# Power.net
KiCad netlist of a schematic drawn in Altium Designer
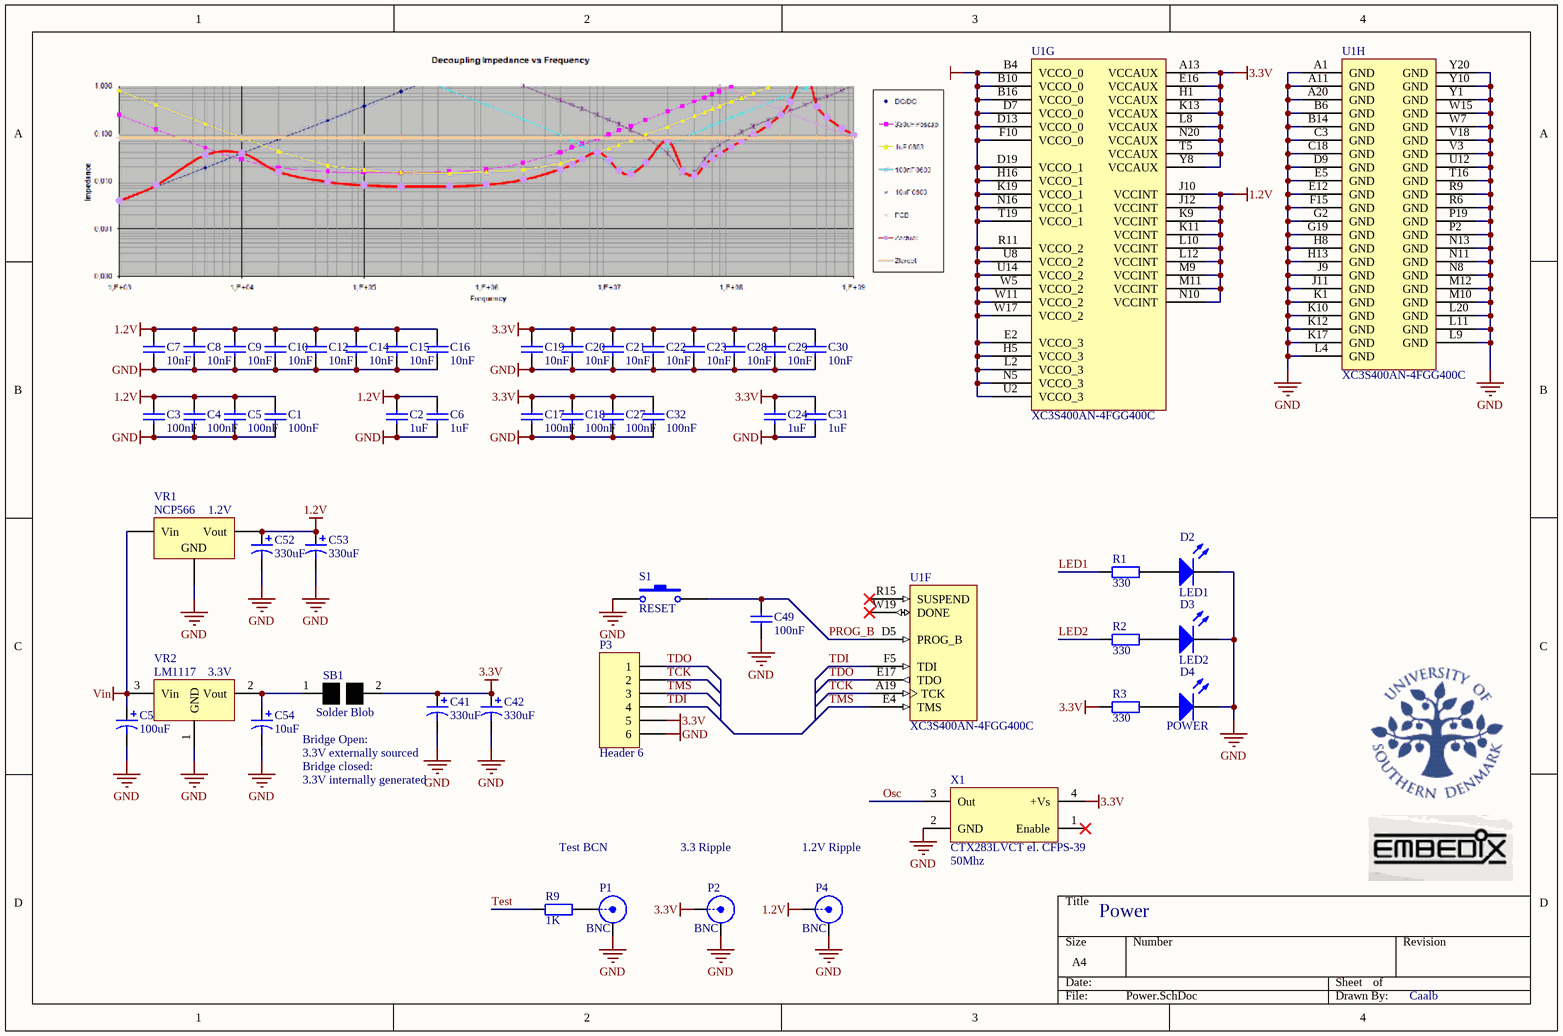
[diagram p0: Power.SchDoc]

(export (version "E")
  (design (tool "Eeschema 10.0.6"))
  (components
    (comp (ref "C1")
      (value "100nF")
      (footprint "0603")
      (description "!Capacitor")
      (fields (field (name "Comment") "Cap") (field (name "PUBLISHER") "Altium Limited"))
      (libsource (lib "Miscellaneous Devices") (part "Cap"))
    )
    (comp (ref "C2")
      (value "1uF")
      (footprint "0603")
      (description "!Capacitor")
      (fields (field (name "Comment") "Cap") (field (name "PUBLISHER") "Altium Limited"))
      (libsource (lib "Miscellaneous Devices") (part "Cap"))
    )
    (comp (ref "C3")
      (value "100nF")
      (footprint "0603")
      (description "!Capacitor")
      (fields (field (name "Comment") "Cap") (field (name "PUBLISHER") "Altium Limited"))
      (libsource (lib "Miscellaneous Devices") (part "Cap"))
    )
    (comp (ref "C4")
      (value "100nF")
      (footprint "0603")
      (description "!Capacitor")
      (fields (field (name "Comment") "Cap") (field (name "PUBLISHER") "Altium Limited"))
      (libsource (lib "Miscellaneous Devices") (part "Cap"))
    )
    (comp (ref "C5")
      (value "100nF")
      (footprint "0603")
      (description "!Capacitor")
      (fields (field (name "Comment") "Cap") (field (name "PUBLISHER") "Altium Limited"))
      (libsource (lib "Miscellaneous Devices") (part "Cap"))
    )
    (comp (ref "C6")
      (value "1uF")
      (footprint "0603")
      (description "!Capacitor")
      (fields (field (name "Comment") "Cap") (field (name "PUBLISHER") "Altium Limited"))
      (libsource (lib "Miscellaneous Devices") (part "Cap"))
    )
    (comp (ref "C7")
      (value "10nF")
      (footprint "0603")
      (description "!Capacitor")
      (fields (field (name "Comment") "Cap") (field (name "PUBLISHER") "Altium Limited"))
      (libsource (lib "Miscellaneous Devices") (part "Cap"))
    )
    (comp (ref "C8")
      (value "10nF")
      (footprint "0603")
      (description "!Capacitor")
      (fields (field (name "Comment") "Cap") (field (name "PUBLISHER") "Altium Limited"))
      (libsource (lib "Miscellaneous Devices") (part "Cap"))
    )
    (comp (ref "C9")
      (value "10nF")
      (footprint "0603")
      (description "!Capacitor")
      (fields (field (name "Comment") "Cap") (field (name "PUBLISHER") "Altium Limited"))
      (libsource (lib "Miscellaneous Devices") (part "Cap"))
    )
    (comp (ref "C10")
      (value "10nF")
      (footprint "0603")
      (description "!Capacitor")
      (fields (field (name "Comment") "Cap") (field (name "PUBLISHER") "Altium Limited"))
      (libsource (lib "Miscellaneous Devices") (part "Cap"))
    )
    (comp (ref "C12")
      (value "10nF")
      (footprint "0603")
      (description "!Capacitor")
      (fields (field (name "Comment") "Cap") (field (name "PUBLISHER") "Altium Limited"))
      (libsource (lib "Miscellaneous Devices") (part "Cap"))
    )
    (comp (ref "C14")
      (value "10nF")
      (footprint "0603")
      (description "!Capacitor")
      (fields (field (name "Comment") "Cap") (field (name "PUBLISHER") "Altium Limited"))
      (libsource (lib "Miscellaneous Devices") (part "Cap"))
    )
    (comp (ref "C15")
      (value "10nF")
      (footprint "0603")
      (description "!Capacitor")
      (fields (field (name "Comment") "Cap") (field (name "PUBLISHER") "Altium Limited"))
      (libsource (lib "Miscellaneous Devices") (part "Cap"))
    )
    (comp (ref "C16")
      (value "10nF")
      (footprint "0603")
      (description "!Capacitor")
      (fields (field (name "Comment") "Cap") (field (name "PUBLISHER") "Altium Limited"))
      (libsource (lib "Miscellaneous Devices") (part "Cap"))
    )
    (comp (ref "C17")
      (value "100nF")
      (footprint "0603")
      (description "!Capacitor")
      (fields (field (name "Comment") "Cap") (field (name "PUBLISHER") "Altium Limited"))
      (libsource (lib "Miscellaneous Devices") (part "Cap"))
    )
    (comp (ref "C18")
      (value "100nF")
      (footprint "0603")
      (description "!Capacitor")
      (fields (field (name "Comment") "Cap") (field (name "PUBLISHER") "Altium Limited"))
      (libsource (lib "Miscellaneous Devices") (part "Cap"))
    )
    (comp (ref "C19")
      (value "10nF")
      (footprint "0603")
      (description "!Capacitor")
      (fields (field (name "Comment") "Cap") (field (name "PUBLISHER") "Altium Limited"))
      (libsource (lib "Miscellaneous Devices") (part "Cap"))
    )
    (comp (ref "C20")
      (value "10nF")
      (footprint "0603")
      (description "!Capacitor")
      (fields (field (name "Comment") "Cap") (field (name "PUBLISHER") "Altium Limited"))
      (libsource (lib "Miscellaneous Devices") (part "Cap"))
    )
    (comp (ref "C21")
      (value "10nF")
      (footprint "0603")
      (description "!Capacitor")
      (fields (field (name "Comment") "Cap") (field (name "PUBLISHER") "Altium Limited"))
      (libsource (lib "Miscellaneous Devices") (part "Cap"))
    )
    (comp (ref "C22")
      (value "10nF")
      (footprint "0603")
      (description "!Capacitor")
      (fields (field (name "Comment") "Cap") (field (name "PUBLISHER") "Altium Limited"))
      (libsource (lib "Miscellaneous Devices") (part "Cap"))
    )
    (comp (ref "C23")
      (value "10nF")
      (footprint "0603")
      (description "!Capacitor")
      (fields (field (name "Comment") "Cap") (field (name "PUBLISHER") "Altium Limited"))
      (libsource (lib "Miscellaneous Devices") (part "Cap"))
    )
    (comp (ref "C24")
      (value "1uF")
      (footprint "0603")
      (description "!Capacitor")
      (fields (field (name "Comment") "Cap") (field (name "PUBLISHER") "Altium Limited"))
      (libsource (lib "Miscellaneous Devices") (part "Cap"))
    )
    (comp (ref "C27")
      (value "100nF")
      (footprint "0603")
      (description "!Capacitor")
      (fields (field (name "Comment") "Cap") (field (name "PUBLISHER") "Altium Limited"))
      (libsource (lib "Miscellaneous Devices") (part "Cap"))
    )
    (comp (ref "C28")
      (value "10nF")
      (footprint "0603")
      (description "!Capacitor")
      (fields (field (name "Comment") "Cap") (field (name "PUBLISHER") "Altium Limited"))
      (libsource (lib "Miscellaneous Devices") (part "Cap"))
    )
    (comp (ref "C29")
      (value "10nF")
      (footprint "0603")
      (description "!Capacitor")
      (fields (field (name "Comment") "Cap") (field (name "PUBLISHER") "Altium Limited"))
      (libsource (lib "Miscellaneous Devices") (part "Cap"))
    )
    (comp (ref "C30")
      (value "10nF")
      (footprint "0603")
      (description "!Capacitor")
      (fields (field (name "Comment") "Cap") (field (name "PUBLISHER") "Altium Limited"))
      (libsource (lib "Miscellaneous Devices") (part "Cap"))
    )
    (comp (ref "C31")
      (value "1uF")
      (footprint "0603")
      (description "!Capacitor")
      (fields (field (name "Comment") "Cap") (field (name "PUBLISHER") "Altium Limited"))
      (libsource (lib "Miscellaneous Devices") (part "Cap"))
    )
    (comp (ref "C32")
      (value "100nF")
      (footprint "0603")
      (description "!Capacitor")
      (fields (field (name "Comment") "Cap") (field (name "PUBLISHER") "Altium Limited"))
      (libsource (lib "Miscellaneous Devices") (part "Cap"))
    )
    (comp (ref "C41")
      (value "330uF")
      (footprint "Tantal size X")
      (description "!Polarized Capacitor (Radial)")
      (fields (field (name "Comment") "Cap Pol1") (field (name "PUBLISHER") "Altium Limited"))
      (libsource (lib "Miscellaneous Devices") (part "Cap Pol1"))
    )
    (comp (ref "C42")
      (value "330uF")
      (footprint "Tantal size X")
      (description "!Polarized Capacitor (Radial)")
      (fields (field (name "Comment") "Cap Pol1") (field (name "PUBLISHER") "Altium Limited"))
      (libsource (lib "Miscellaneous Devices") (part "Cap Pol1"))
    )
    (comp (ref "C49")
      (value "100nF")
      (footprint "0603")
      (description "!Capacitor")
      (fields (field (name "Comment") "Cap") (field (name "PUBLISHER") "Altium Limited"))
      (libsource (lib "") (part "Cap_1"))
    )
    (comp (ref "C51")
      (value "100uF")
      (footprint "Tantal size X")
      (description "!Polarized Capacitor (Radial)")
      (fields (field (name "Comment") "Cap Pol1") (field (name "PUBLISHER") "Altium Limited"))
      (libsource (lib "Miscellaneous Devices") (part "Cap Pol1"))
    )
    (comp (ref "C52")
      (value "330uF")
      (footprint "Tantal size X")
      (description "!Polarized Capacitor (Radial)")
      (fields (field (name "Comment") "Cap Pol1") (field (name "PUBLISHER") "Altium Limited"))
      (libsource (lib "Miscellaneous Devices") (part "Cap Pol1"))
    )
    (comp (ref "C53")
      (value "330uF")
      (footprint "Tantal size X")
      (description "!Polarized Capacitor (Radial)")
      (fields (field (name "Comment") "Cap Pol1") (field (name "PUBLISHER") "Altium Limited"))
      (libsource (lib "Miscellaneous Devices") (part "Cap Pol1"))
    )
    (comp (ref "C54")
      (value "10uF")
      (footprint "1206Pol")
      (description "!Polarized Capacitor (Radial)")
      (fields (field (name "Comment") "Cap Pol1") (field (name "PUBLISHER") "Altium Limited"))
      (libsource (lib "Miscellaneous Devices") (part "Cap Pol1"))
    )
    (comp (ref "D2")
      (value "LED1")
      (footprint "LED0805")
      (description "LED")
      (fields (field (name "PUBLISHER") "Altium Limited"))
      (libsource (lib "Miscellaneous Devices") (part "LED0"))
    )
    (comp (ref "D3")
      (value "LED2")
      (footprint "LED0805")
      (description "LED")
      (fields (field (name "PUBLISHER") "Altium Limited"))
      (libsource (lib "Miscellaneous Devices") (part "LED0"))
    )
    (comp (ref "D4")
      (value "POWER")
      (footprint "LED0805")
      (description "LED")
      (fields (field (name "PUBLISHER") "Altium Limited"))
      (libsource (lib "Miscellaneous Devices") (part "LED0"))
    )
    (comp (ref "P1")
      (value "BNC")
      (footprint "Miniature Coaxial Connectors")
      (description "Miniature Coaxial Connectors")
      (fields (field (name "PUBLISHER") "Altium Limited"))
      (libsource (lib "Miscellaneous Connectors") (part "BNC"))
    )
    (comp (ref "P2")
      (value "BNC")
      (footprint "Miniature Coaxial Connectors")
      (description "Miniature Coaxial Connectors")
      (fields (field (name "PUBLISHER") "Altium Limited"))
      (libsource (lib "Miscellaneous Connectors") (part "BNC"))
    )
    (comp (ref "P3")
      (value "Header 6")
      (footprint "HDR1X6")
      (description "Header, 6-Pin")
      (fields (field (name "PUBLISHER") "Altium Limited"))
      (libsource (lib "Miscellaneous Connectors") (part "Header 6"))
    )
    (comp (ref "P4")
      (value "BNC")
      (footprint "Miniature Coaxial Connectors")
      (description "Miniature Coaxial Connectors")
      (fields (field (name "PUBLISHER") "Altium Limited"))
      (libsource (lib "Miscellaneous Connectors") (part "BNC"))
    )
    (comp (ref "R1")
      (value "330")
      (footprint "0805")
      (description "!Resistor")
      (fields (field (name "Comment") "Res2") (field (name "PUBLISHER") "Altium Limited"))
      (libsource (lib "") (part "Res2_1"))
    )
    (comp (ref "R2")
      (value "330")
      (footprint "0805")
      (description "!Resistor")
      (fields (field (name "Comment") "Res2") (field (name "PUBLISHER") "Altium Limited"))
      (libsource (lib "") (part "Res2_1"))
    )
    (comp (ref "R3")
      (value "330")
      (footprint "0805")
      (description "!Resistor")
      (fields (field (name "Comment") "Res2") (field (name "PUBLISHER") "Altium Limited"))
      (libsource (lib "") (part "Res2_1"))
    )
    (comp (ref "R9")
      (value "1K")
      (footprint "0603")
      (description "!Resistor")
      (fields (field (name "Comment") "Res2") (field (name "PUBLISHER") "Altium Limited"))
      (libsource (lib "Miscellaneous Devices") (part "Res2"))
    )
    (comp (ref "S1")
      (value "RESET")
      (footprint "B3U-3000P")
      (description "Switch")
      (fields (field (name "PUBLISHER") "Altium Limited"))
      (libsource (lib "Miscellaneous Devices") (part "SW-PB"))
    )
    (comp (ref "SB1")
      (value "Solder Blob")
      (footprint "0805 v.solder_blob")
      (fields
        (field (name "ALTIUM_UNNAMED_1") "Bridge Open:")
        (field (name "ALTIUM_UNNAMED_2") "Bridge closed:")
        (field (name "ALTIUM_UNNAMED_3") "3.3V externally sourced")
        (field (name "ALTIUM_UNNAMED_4") "3.3V internally generated")
      )
      (libsource (lib "DivLib") (part "Jumper"))
    )
    (comp (ref "U1")
      (value "XC3S400AN-4FGG400C")
      (footprint "FGG400")
      (fields (field (name "PUBLISHER") "Altium Limited"))
      (libsource (lib "Xilinx Spartan-3AN") (part "XC3S400AN-4FGG400C"))
    )
    (comp (ref "VR1")
      (value "NCP566")
      (footprint "SOT-223")
      (description "Volt Reg NCP566")
      (fields (field (name "ALTIUM_VALUE") "1.2V") (field (name "PUBLISHER") "Altium Limited"))
      (libsource (lib "Miscellaneous Devices") (part "Volt Reg"))
    )
    (comp (ref "VR2")
      (value "LM1117")
      (footprint "SOT-223")
      (description "800mA Low-Dropout Linear Regulator")
      (fields (field (name "ALTIUM_VALUE") "3.3V"))
      (libsource (lib "DivLib") (part "LM1117"))
    )
    (comp (ref "X1")
      (value "CTX283LVCT el. CFPS-39")
      (footprint "CB3LV-3C-50M0000")
      (description "3.3V, ultra minature surface mount oscillator")
      (fields (field (name "ALTIUM_VALUE") "50Mhz"))
      (libsource (lib "DivLib") (part "CFPS-39"))
    )
  )
  (nets
    (net (code "1") (name "/LED1") (class "Default")
      (node (ref "R1") (pin "2") (pinfunction "2_2") (pintype "passive"))
    )
    (net (code "2") (name "/LED2") (class "Default")
      (node (ref "R2") (pin "2") (pinfunction "2_2") (pintype "passive"))
    )
    (net (code "3") (name "/Osc") (class "Default")
      (node (ref "X1") (pin "3") (pinfunction "Out_3") (pintype "power_in"))
    )
    (net (code "4") (name "/PROG_B") (class "Default")
      (node (ref "C49") (pin "2") (pinfunction "2_2") (pintype "passive"))
      (node (ref "S1") (pin "2") (pinfunction "2_2") (pintype "passive"))
      (node (ref "U1") (pin "D5") (pinfunction "PROG_B_D5") (pintype "input"))
    )
    (net (code "5") (name "/TCK") (class "Default")
      (node (ref "P3") (pin "2") (pinfunction "2_2") (pintype "passive"))
      (node (ref "U1") (pin "A19") (pinfunction "TCK_A19") (pintype "input"))
    )
    (net (code "6") (name "/TDI") (class "Default")
      (node (ref "P3") (pin "4") (pinfunction "4_4") (pintype "passive"))
      (node (ref "U1") (pin "F5") (pinfunction "TDI_F5") (pintype "input"))
    )
    (net (code "7") (name "/TDO") (class "Default")
      (node (ref "P3") (pin "1") (pinfunction "1_1") (pintype "passive"))
      (node (ref "U1") (pin "E17") (pinfunction "TDO_E17") (pintype "output"))
    )
    (net (code "8") (name "/TMS") (class "Default")
      (node (ref "P3") (pin "3") (pinfunction "3_3") (pintype "passive"))
      (node (ref "U1") (pin "E4") (pinfunction "TMS_E4") (pintype "input"))
    )
    (net (code "9") (name "/Test") (class "Default")
      (node (ref "R9") (pin "1") (pinfunction "1_1") (pintype "passive"))
    )
    (net (code "10") (name "1.2V") (class "Default")
      (node (ref "C1") (pin "2") (pinfunction "2_2") (pintype "passive"))
      (node (ref "C10") (pin "2") (pinfunction "2_2") (pintype "passive"))
      (node (ref "C12") (pin "2") (pinfunction "2_2") (pintype "passive"))
      (node (ref "C14") (pin "2") (pinfunction "2_2") (pintype "passive"))
      (node (ref "C15") (pin "2") (pinfunction "2_2") (pintype "passive"))
      (node (ref "C16") (pin "2") (pinfunction "2_2") (pintype "passive"))
      (node (ref "C2") (pin "2") (pinfunction "2_2") (pintype "passive"))
      (node (ref "C3") (pin "2") (pinfunction "2_2") (pintype "passive"))
      (node (ref "C4") (pin "2") (pinfunction "2_2") (pintype "passive"))
      (node (ref "C5") (pin "2") (pinfunction "2_2") (pintype "passive"))
      (node (ref "C52") (pin "1") (pinfunction "1_1") (pintype "passive"))
      (node (ref "C53") (pin "1") (pinfunction "1_1") (pintype "passive"))
      (node (ref "C6") (pin "2") (pinfunction "2_2") (pintype "passive"))
      (node (ref "C7") (pin "2") (pinfunction "2_2") (pintype "passive"))
      (node (ref "C8") (pin "2") (pinfunction "2_2") (pintype "passive"))
      (node (ref "C9") (pin "2") (pinfunction "2_2") (pintype "passive"))
      (node (ref "P4") (pin "1") (pinfunction "X_1") (pintype "passive"))
      (node (ref "U1") (pin "J10") (pinfunction "VCCINT_J10") (pintype "power_in"))
      (node (ref "U1") (pin "J12") (pinfunction "VCCINT_J12") (pintype "power_in"))
      (node (ref "U1") (pin "K11") (pinfunction "VCCINT_K11") (pintype "power_in"))
      (node (ref "U1") (pin "K9") (pinfunction "VCCINT_K9") (pintype "power_in"))
      (node (ref "U1") (pin "L10") (pinfunction "VCCINT_L10") (pintype "power_in"))
      (node (ref "U1") (pin "L12") (pinfunction "VCCINT_L12") (pintype "power_in"))
      (node (ref "U1") (pin "M11") (pinfunction "VCCINT_M11") (pintype "power_in"))
      (node (ref "U1") (pin "M9") (pinfunction "VCCINT_M9") (pintype "power_in"))
      (node (ref "U1") (pin "N10") (pinfunction "VCCINT_N10") (pintype "power_in"))
      (node (ref "VR1") (pin "3") (pinfunction "Vout_3") (pintype "passive"))
    )
    (net (code "11") (name "3.3V") (class "Default")
      (node (ref "C17") (pin "2") (pinfunction "2_2") (pintype "passive"))
      (node (ref "C18") (pin "2") (pinfunction "2_2") (pintype "passive"))
      (node (ref "C19") (pin "2") (pinfunction "2_2") (pintype "passive"))
      (node (ref "C20") (pin "2") (pinfunction "2_2") (pintype "passive"))
      (node (ref "C21") (pin "2") (pinfunction "2_2") (pintype "passive"))
      (node (ref "C22") (pin "2") (pinfunction "2_2") (pintype "passive"))
      (node (ref "C23") (pin "2") (pinfunction "2_2") (pintype "passive"))
      (node (ref "C24") (pin "2") (pinfunction "2_2") (pintype "passive"))
      (node (ref "C27") (pin "2") (pinfunction "2_2") (pintype "passive"))
      (node (ref "C28") (pin "2") (pinfunction "2_2") (pintype "passive"))
      (node (ref "C29") (pin "2") (pinfunction "2_2") (pintype "passive"))
      (node (ref "C30") (pin "2") (pinfunction "2_2") (pintype "passive"))
      (node (ref "C31") (pin "2") (pinfunction "2_2") (pintype "passive"))
      (node (ref "C32") (pin "2") (pinfunction "2_2") (pintype "passive"))
      (node (ref "C41") (pin "1") (pinfunction "1_1") (pintype "passive"))
      (node (ref "C42") (pin "1") (pinfunction "1_1") (pintype "passive"))
      (node (ref "P2") (pin "1") (pinfunction "X_1") (pintype "passive"))
      (node (ref "P3") (pin "5") (pinfunction "5_5") (pintype "passive"))
      (node (ref "R3") (pin "2") (pinfunction "2_2") (pintype "passive"))
      (node (ref "SB1") (pin "2") (pinfunction "2_2") (pintype "passive"))
      (node (ref "U1") (pin "A13") (pinfunction "VCCAUX_A13") (pintype "power_in"))
      (node (ref "U1") (pin "B10") (pinfunction "VCCO_0_B10") (pintype "power_in"))
      (node (ref "U1") (pin "B16") (pinfunction "VCCO_0_B16") (pintype "power_in"))
      (node (ref "U1") (pin "B4") (pinfunction "VCCO_0_B4") (pintype "power_in"))
      (node (ref "U1") (pin "D13") (pinfunction "VCCO_0_D13") (pintype "power_in"))
      (node (ref "U1") (pin "D19") (pinfunction "VCCO_1_D19") (pintype "power_in"))
      (node (ref "U1") (pin "D7") (pinfunction "VCCO_0_D7") (pintype "power_in"))
      (node (ref "U1") (pin "E16") (pinfunction "VCCAUX_E16") (pintype "power_in"))
      (node (ref "U1") (pin "E2") (pinfunction "VCCO_3_E2") (pintype "power_in"))
      (node (ref "U1") (pin "F10") (pinfunction "VCCO_0_F10") (pintype "power_in"))
      (node (ref "U1") (pin "H1") (pinfunction "VCCAUX_H1") (pintype "power_in"))
      (node (ref "U1") (pin "H16") (pinfunction "VCCO_1_H16") (pintype "power_in"))
      (node (ref "U1") (pin "H5") (pinfunction "VCCO_3_H5") (pintype "power_in"))
      (node (ref "U1") (pin "K13") (pinfunction "VCCAUX_K13") (pintype "power_in"))
      (node (ref "U1") (pin "K19") (pinfunction "VCCO_1_K19") (pintype "power_in"))
      (node (ref "U1") (pin "L2") (pinfunction "VCCO_3_L2") (pintype "power_in"))
      (node (ref "U1") (pin "L8") (pinfunction "VCCAUX_L8") (pintype "power_in"))
      (node (ref "U1") (pin "N16") (pinfunction "VCCO_1_N16") (pintype "power_in"))
      (node (ref "U1") (pin "N20") (pinfunction "VCCAUX_N20") (pintype "power_in"))
      (node (ref "U1") (pin "N5") (pinfunction "VCCO_3_N5") (pintype "power_in"))
      (node (ref "U1") (pin "R11") (pinfunction "VCCO_2_R11") (pintype "power_in"))
      (node (ref "U1") (pin "T19") (pinfunction "VCCO_1_T19") (pintype "power_in"))
      (node (ref "U1") (pin "T5") (pinfunction "VCCAUX_T5") (pintype "power_in"))
      (node (ref "U1") (pin "U14") (pinfunction "VCCO_2_U14") (pintype "power_in"))
      (node (ref "U1") (pin "U2") (pinfunction "VCCO_3_U2") (pintype "power_in"))
      (node (ref "U1") (pin "U8") (pinfunction "VCCO_2_U8") (pintype "power_in"))
      (node (ref "U1") (pin "W11") (pinfunction "VCCO_2_W11") (pintype "power_in"))
      (node (ref "U1") (pin "W17") (pinfunction "VCCO_2_W17") (pintype "power_in"))
      (node (ref "U1") (pin "W5") (pinfunction "VCCO_2_W5") (pintype "power_in"))
      (node (ref "U1") (pin "Y8") (pinfunction "VCCAUX_Y8") (pintype "power_in"))
      (node (ref "X1") (pin "4") (pinfunction "+Vs_4") (pintype "power_in"))
    )
    (net (code "12") (name "GND") (class "Default")
      (node (ref "C1") (pin "1") (pinfunction "1_1") (pintype "passive"))
      (node (ref "C10") (pin "1") (pinfunction "1_1") (pintype "passive"))
      (node (ref "C12") (pin "1") (pinfunction "1_1") (pintype "passive"))
      (node (ref "C14") (pin "1") (pinfunction "1_1") (pintype "passive"))
      (node (ref "C15") (pin "1") (pinfunction "1_1") (pintype "passive"))
      (node (ref "C16") (pin "1") (pinfunction "1_1") (pintype "passive"))
      (node (ref "C17") (pin "1") (pinfunction "1_1") (pintype "passive"))
      (node (ref "C18") (pin "1") (pinfunction "1_1") (pintype "passive"))
      (node (ref "C19") (pin "1") (pinfunction "1_1") (pintype "passive"))
      (node (ref "C2") (pin "1") (pinfunction "1_1") (pintype "passive"))
      (node (ref "C20") (pin "1") (pinfunction "1_1") (pintype "passive"))
      (node (ref "C21") (pin "1") (pinfunction "1_1") (pintype "passive"))
      (node (ref "C22") (pin "1") (pinfunction "1_1") (pintype "passive"))
      (node (ref "C23") (pin "1") (pinfunction "1_1") (pintype "passive"))
      (node (ref "C24") (pin "1") (pinfunction "1_1") (pintype "passive"))
      (node (ref "C27") (pin "1") (pinfunction "1_1") (pintype "passive"))
      (node (ref "C28") (pin "1") (pinfunction "1_1") (pintype "passive"))
      (node (ref "C29") (pin "1") (pinfunction "1_1") (pintype "passive"))
      (node (ref "C3") (pin "1") (pinfunction "1_1") (pintype "passive"))
      (node (ref "C30") (pin "1") (pinfunction "1_1") (pintype "passive"))
      (node (ref "C31") (pin "1") (pinfunction "1_1") (pintype "passive"))
      (node (ref "C32") (pin "1") (pinfunction "1_1") (pintype "passive"))
      (node (ref "C4") (pin "1") (pinfunction "1_1") (pintype "passive"))
      (node (ref "C41") (pin "2") (pinfunction "2_2") (pintype "passive"))
      (node (ref "C42") (pin "2") (pinfunction "2_2") (pintype "passive"))
      (node (ref "C49") (pin "1") (pinfunction "1_1") (pintype "passive"))
      (node (ref "C5") (pin "1") (pinfunction "1_1") (pintype "passive"))
      (node (ref "C51") (pin "2") (pinfunction "2_2") (pintype "passive"))
      (node (ref "C52") (pin "2") (pinfunction "2_2") (pintype "passive"))
      (node (ref "C53") (pin "2") (pinfunction "2_2") (pintype "passive"))
      (node (ref "C54") (pin "2") (pinfunction "2_2") (pintype "passive"))
      (node (ref "C6") (pin "1") (pinfunction "1_1") (pintype "passive"))
      (node (ref "C7") (pin "1") (pinfunction "1_1") (pintype "passive"))
      (node (ref "C8") (pin "1") (pinfunction "1_1") (pintype "passive"))
      (node (ref "C9") (pin "1") (pinfunction "1_1") (pintype "passive"))
      (node (ref "D2") (pin "2") (pinfunction "K_2") (pintype "passive"))
      (node (ref "D3") (pin "2") (pinfunction "K_2") (pintype "passive"))
      (node (ref "D4") (pin "2") (pinfunction "K_2") (pintype "passive"))
      (node (ref "P1") (pin "2") (pinfunction "Y_2") (pintype "passive"))
      (node (ref "P2") (pin "2") (pinfunction "Y_2") (pintype "passive"))
      (node (ref "P3") (pin "6") (pinfunction "6_6") (pintype "passive"))
      (node (ref "P4") (pin "2") (pinfunction "Y_2") (pintype "passive"))
      (node (ref "S1") (pin "1") (pinfunction "1_1") (pintype "passive"))
      (node (ref "U1") (pin "A1") (pinfunction "GND_A1") (pintype "power_in"))
      (node (ref "U1") (pin "A11") (pinfunction "GND_A11") (pintype "power_in"))
      (node (ref "U1") (pin "A20") (pinfunction "GND_A20") (pintype "power_in"))
      (node (ref "U1") (pin "B14") (pinfunction "GND_B14") (pintype "power_in"))
      (node (ref "U1") (pin "B6") (pinfunction "GND_B6") (pintype "power_in"))
      (node (ref "U1") (pin "C18") (pinfunction "GND_C18") (pintype "power_in"))
      (node (ref "U1") (pin "C3") (pinfunction "GND_C3") (pintype "power_in"))
      (node (ref "U1") (pin "D9") (pinfunction "GND_D9") (pintype "power_in"))
      (node (ref "U1") (pin "E12") (pinfunction "GND_E12") (pintype "power_in"))
      (node (ref "U1") (pin "E5") (pinfunction "GND_E5") (pintype "power_in"))
      (node (ref "U1") (pin "F15") (pinfunction "GND_F15") (pintype "power_in"))
      (node (ref "U1") (pin "G19") (pinfunction "GND_G19") (pintype "power_in"))
      (node (ref "U1") (pin "G2") (pinfunction "GND_G2") (pintype "power_in"))
      (node (ref "U1") (pin "H13") (pinfunction "GND_H13") (pintype "power_in"))
      (node (ref "U1") (pin "H8") (pinfunction "GND_H8") (pintype "power_in"))
      (node (ref "U1") (pin "J11") (pinfunction "GND_J11") (pintype "power_in"))
      (node (ref "U1") (pin "J9") (pinfunction "GND_J9") (pintype "power_in"))
      (node (ref "U1") (pin "K1") (pinfunction "GND_K1") (pintype "power_in"))
      (node (ref "U1") (pin "K10") (pinfunction "GND_K10") (pintype "power_in"))
      (node (ref "U1") (pin "K12") (pinfunction "GND_K12") (pintype "power_in"))
      (node (ref "U1") (pin "K17") (pinfunction "GND_K17") (pintype "power_in"))
      (node (ref "U1") (pin "L11") (pinfunction "GND_L11") (pintype "power_in"))
      (node (ref "U1") (pin "L20") (pinfunction "GND_L20") (pintype "power_in"))
      (node (ref "U1") (pin "L4") (pinfunction "GND_L4") (pintype "power_in"))
      (node (ref "U1") (pin "L9") (pinfunction "GND_L9") (pintype "power_in"))
      (node (ref "U1") (pin "M10") (pinfunction "GND_M10") (pintype "power_in"))
      (node (ref "U1") (pin "M12") (pinfunction "GND_M12") (pintype "power_in"))
      (node (ref "U1") (pin "N11") (pinfunction "GND_N11") (pintype "power_in"))
      (node (ref "U1") (pin "N13") (pinfunction "GND_N13") (pintype "power_in"))
      (node (ref "U1") (pin "N8") (pinfunction "GND_N8") (pintype "power_in"))
      (node (ref "U1") (pin "P19") (pinfunction "GND_P19") (pintype "power_in"))
      (node (ref "U1") (pin "P2") (pinfunction "GND_P2") (pintype "power_in"))
      (node (ref "U1") (pin "R6") (pinfunction "GND_R6") (pintype "power_in"))
      (node (ref "U1") (pin "R9") (pinfunction "GND_R9") (pintype "power_in"))
      (node (ref "U1") (pin "T16") (pinfunction "GND_T16") (pintype "power_in"))
      (node (ref "U1") (pin "U12") (pinfunction "GND_U12") (pintype "power_in"))
      (node (ref "U1") (pin "V18") (pinfunction "GND_V18") (pintype "power_in"))
      (node (ref "U1") (pin "V3") (pinfunction "GND_V3") (pintype "power_in"))
      (node (ref "U1") (pin "W15") (pinfunction "GND_W15") (pintype "power_in"))
      (node (ref "U1") (pin "W7") (pinfunction "GND_W7") (pintype "power_in"))
      (node (ref "U1") (pin "Y1") (pinfunction "GND_Y1") (pintype "power_in"))
      (node (ref "U1") (pin "Y10") (pinfunction "GND_Y10") (pintype "power_in"))
      (node (ref "U1") (pin "Y20") (pinfunction "GND_Y20") (pintype "power_in"))
      (node (ref "VR1") (pin "2") (pinfunction "GND_2") (pintype "passive"))
      (node (ref "VR2") (pin "1") (pinfunction "GND_1") (pintype "power_in"))
      (node (ref "X1") (pin "2") (pinfunction "GND_2") (pintype "power_in"))
    )
    (net (code "13") (name "Net-(D2-A)") (class "Default")
      (node (ref "D2") (pin "1") (pinfunction "A_1") (pintype "passive"))
      (node (ref "R1") (pin "1") (pinfunction "1_1") (pintype "passive"))
    )
    (net (code "14") (name "Net-(D3-A)") (class "Default")
      (node (ref "D3") (pin "1") (pinfunction "A_1") (pintype "passive"))
      (node (ref "R2") (pin "1") (pinfunction "1_1") (pintype "passive"))
    )
    (net (code "15") (name "Net-(D4-A)") (class "Default")
      (node (ref "D4") (pin "1") (pinfunction "A_1") (pintype "passive"))
      (node (ref "R3") (pin "1") (pinfunction "1_1") (pintype "passive"))
    )
    (net (code "16") (name "Net-(P1-X)") (class "Default")
      (node (ref "P1") (pin "1") (pinfunction "X_1") (pintype "passive"))
      (node (ref "R9") (pin "2") (pinfunction "2_2") (pintype "passive"))
    )
    (net (code "17") (name "Net-(VR2-Vout)") (class "Default")
      (node (ref "C54") (pin "1") (pinfunction "1_1") (pintype "passive"))
      (node (ref "SB1") (pin "1") (pinfunction "1_1") (pintype "passive"))
      (node (ref "VR2") (pin "2") (pinfunction "Vout_2") (pintype "power_in"))
    )
    (net (code "18") (name "Vin") (class "Default")
      (node (ref "C51") (pin "1") (pinfunction "1_1") (pintype "passive"))
      (node (ref "VR1") (pin "1") (pinfunction "Vin_1") (pintype "passive"))
      (node (ref "VR2") (pin "3") (pinfunction "Vin_3") (pintype "power_in"))
    )
    (net (code "19") (name "unconnected-(U1F-DONE-PadW19)") (class "Default")
      (node (ref "U1") (pin "W19") (pinfunction "DONE_W19") (pintype "bidirectional+no_connect"))
    )
    (net (code "20") (name "unconnected-(U1F-SUSPEND-PadR15)") (class "Default")
      (node (ref "U1") (pin "R15") (pinfunction "SUSPEND_R15") (pintype "input+no_connect"))
    )
    (net (code "21") (name "unconnected-(X1-Enable-Pad1)") (class "Default")
      (node (ref "X1") (pin "1") (pinfunction "Enable_1") (pintype "power_in+no_connect"))
    )
  )
)
